# Blinky555.net
KiCad netlist of a schematic drawn in EAGLE
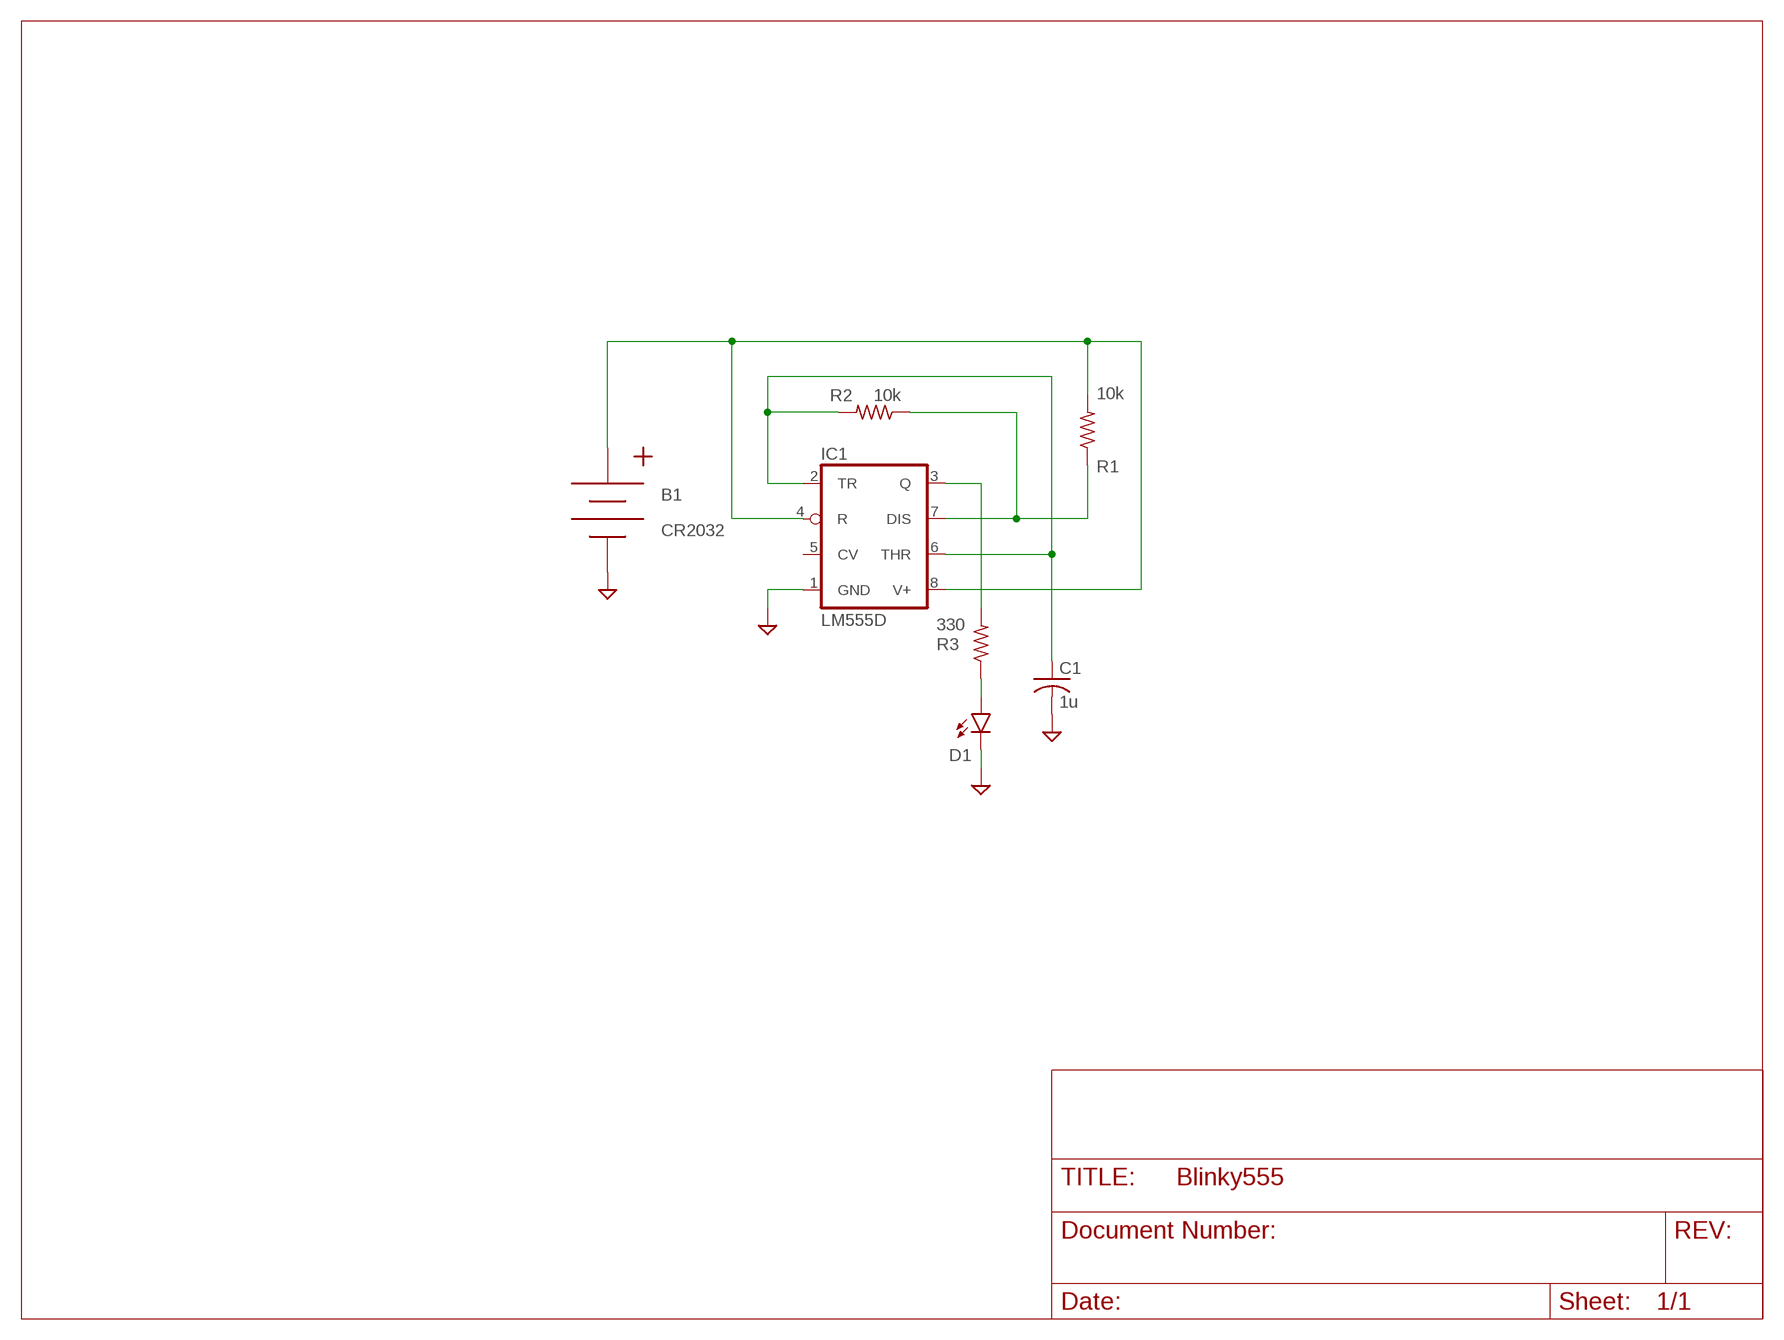
[diagram p0: schematic, sheet 1]

(export (version "E")
  (design (tool "Eeschema 10.0.6"))
  (components
    (comp (ref "B1")
      (value "CR2032")
      (footprint "eagle-import:BATTCON_20MM_4LEGS")
      (libsource (lib "eagle-import") (part "HOLDER_CR2032"))
    )
    (comp (ref "C1")
      (value "1u")
      (footprint "eagle-import:C0805")
      (libsource (lib "eagle-import") (part "CAP"))
    )
    (comp (ref "D1")
      (value "LED")
      (footprint "eagle-import:LED_5MM")
      (libsource (lib "eagle-import") (part "LED"))
    )
    (comp (ref "IC1")
      (value "LM555D")
      (footprint "eagle-import:SO08")
      (libsource (lib "eagle-import") (part "555DLM"))
    )
    (comp (ref "R1")
      (value "10k")
      (footprint "eagle-import:R0805")
      (libsource (lib "eagle-import") (part "RES"))
    )
    (comp (ref "R2")
      (value "10k")
      (footprint "eagle-import:R0805")
      (libsource (lib "eagle-import") (part "RES"))
    )
    (comp (ref "R3")
      (value "330")
      (footprint "eagle-import:R0805")
      (libsource (lib "eagle-import") (part "RES"))
    )
  )
  (nets
    (net (code "1") (name "GND") (class "Default")
      (node (ref "B1") (pin "NEGATIVE") (pinfunction "-_NEGATIVE") (pintype "power_in"))
      (node (ref "C1") (pin "2") (pinfunction "2_2") (pintype "passive"))
      (node (ref "D1") (pin "K") (pinfunction "C_K") (pintype "passive"))
      (node (ref "IC1") (pin "1") (pinfunction "GND_1") (pintype "power_in"))
    )
    (net (code "2") (name "Net-(D1-PadA)") (class "Default")
      (node (ref "D1") (pin "A") (pinfunction "A_A") (pintype "passive"))
      (node (ref "R3") (pin "1") (pinfunction "1_1") (pintype "passive"))
    )
    (net (code "3") (name "Net-(IC1-DIS)") (class "Default")
      (node (ref "IC1") (pin "7") (pinfunction "DIS_7") (pintype "input"))
      (node (ref "R1") (pin "1") (pinfunction "1_1") (pintype "passive"))
      (node (ref "R2") (pin "1") (pinfunction "1_1") (pintype "passive"))
    )
    (net (code "4") (name "Net-(IC1-Q)") (class "Default")
      (node (ref "IC1") (pin "3") (pinfunction "Q_3") (pintype "output"))
      (node (ref "R3") (pin "2") (pinfunction "2_2") (pintype "passive"))
    )
    (net (code "5") (name "Net-(IC1-R)") (class "Default")
      (node (ref "B1") (pin "POSITIVE@1") (pinfunction "+_POSITIVE@1") (pintype "power_in"))
      (node (ref "B1") (pin "POSITIVE@2") (pinfunction "+_POSITIVE@2") (pintype "power_in"))
      (node (ref "B1") (pin "POSITIVE@3") (pinfunction "+_POSITIVE@3") (pintype "power_in"))
      (node (ref "B1") (pin "POSITIVE@4") (pinfunction "+_POSITIVE@4") (pintype "power_in"))
      (node (ref "IC1") (pin "4") (pinfunction "R_4") (pintype "input"))
      (node (ref "IC1") (pin "8") (pinfunction "V+_8") (pintype "power_in"))
      (node (ref "R1") (pin "2") (pinfunction "2_2") (pintype "passive"))
    )
    (net (code "6") (name "Net-(IC1-THR)") (class "Default")
      (node (ref "C1") (pin "1") (pinfunction "1_1") (pintype "passive"))
      (node (ref "IC1") (pin "2") (pinfunction "TR_2") (pintype "input"))
      (node (ref "IC1") (pin "6") (pinfunction "THR_6") (pintype "input"))
      (node (ref "R2") (pin "2") (pinfunction "2_2") (pintype "passive"))
    )
    (net (code "7") (name "unconnected-(IC1-CV-Pad5)") (class "Default")
      (node (ref "IC1") (pin "5") (pinfunction "CV_5") (pintype "input"))
    )
  )
)
